# Smart_Lights_X1.net
KiCad netlist of a schematic drawn in EAGLE
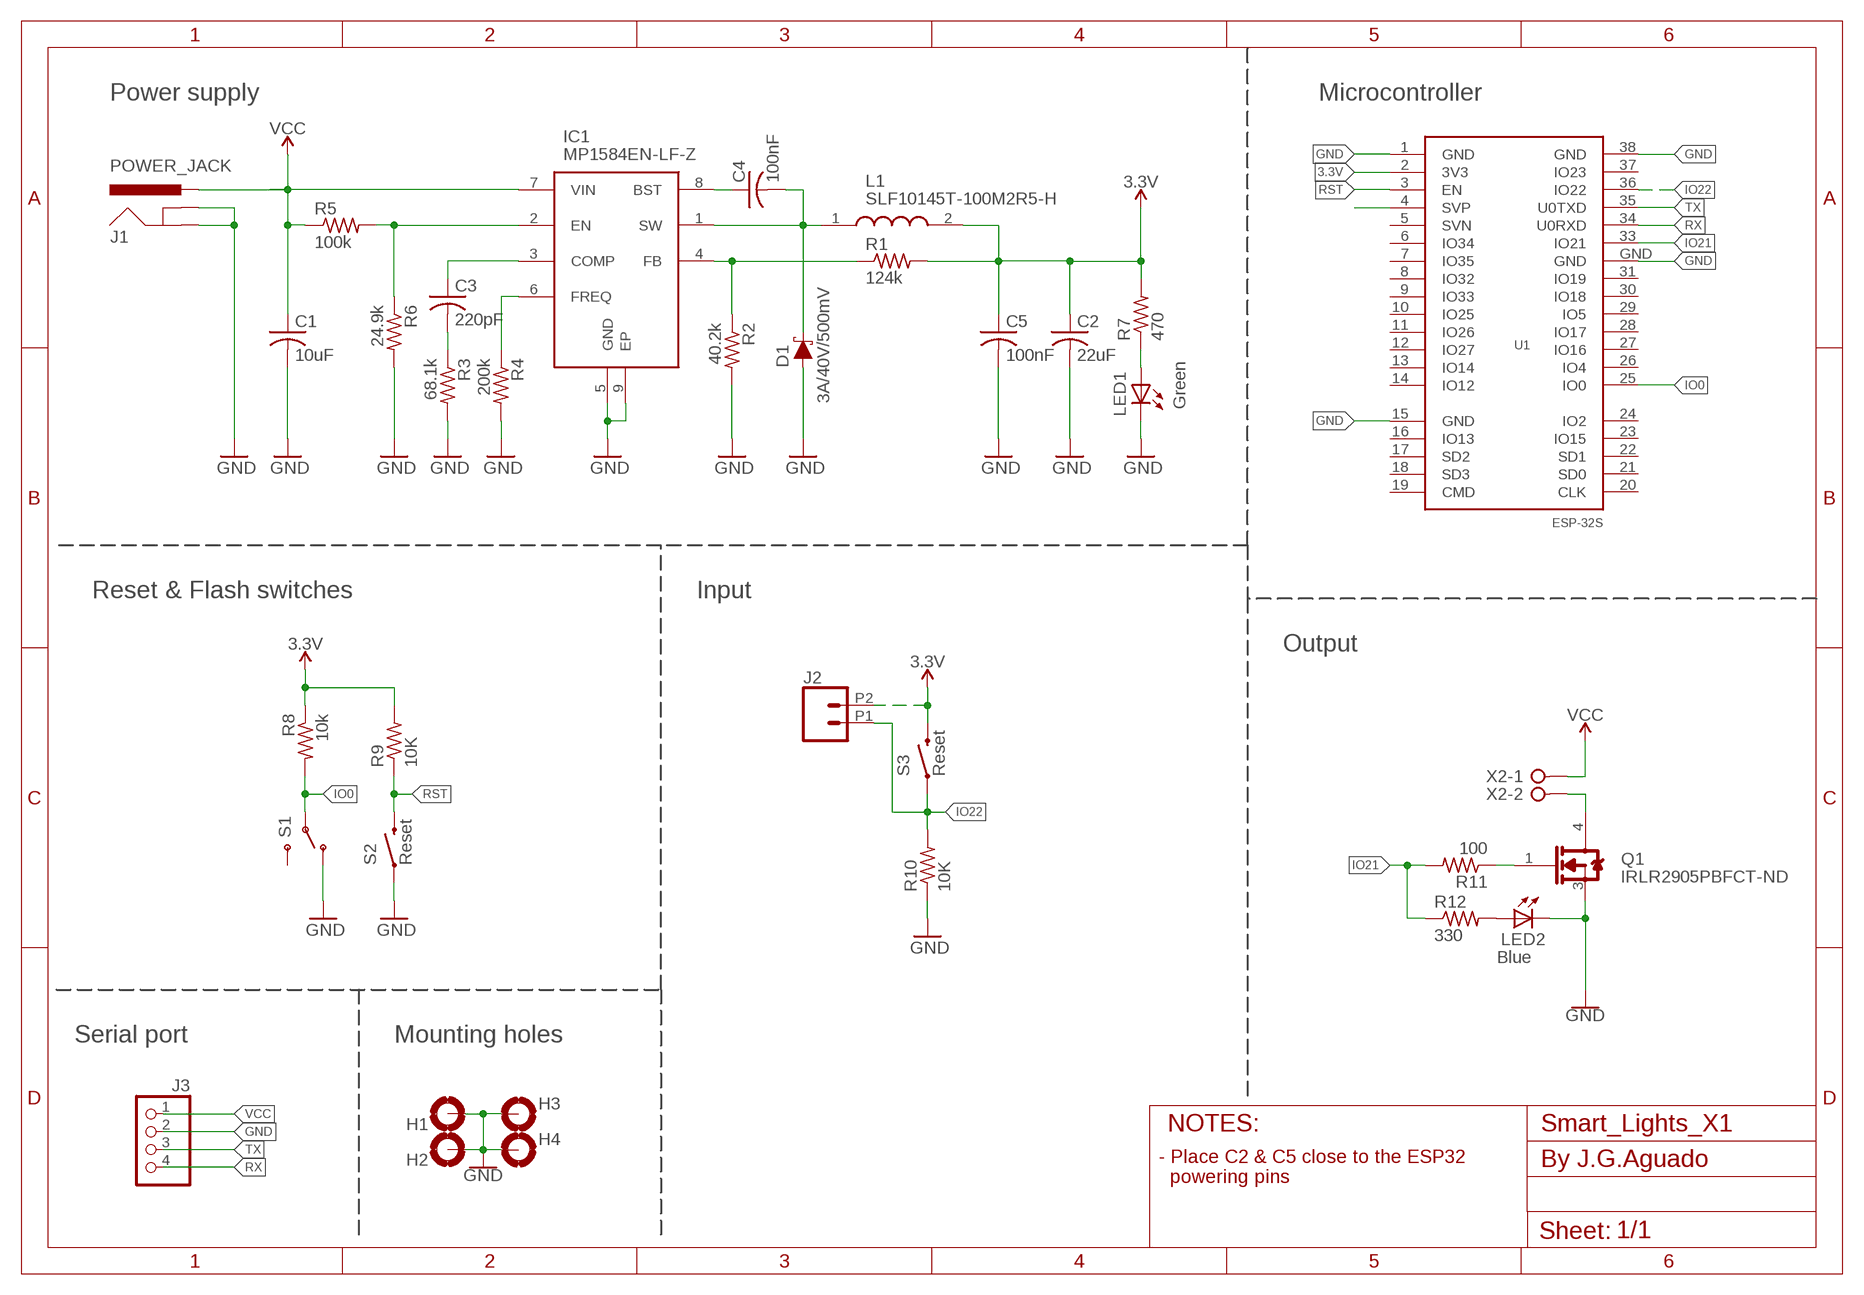
[diagram p0: schematic, sheet 1]

(export (version "E")
  (design (tool "Eeschema 10.0.6"))
  (components
    (comp (ref "C1")
      (value "10uF")
      (footprint "eagle-import:C1206")
      (libsource (lib "eagle-import") (part "C-USC1206"))
    )
    (comp (ref "C2")
      (value "22uF")
      (footprint "eagle-import:C1206")
      (libsource (lib "eagle-import") (part "C-USC1206"))
    )
    (comp (ref "C3")
      (value "220pF")
      (footprint "eagle-import:C1206")
      (libsource (lib "eagle-import") (part "C-USC1206"))
    )
    (comp (ref "C4")
      (value "100nF")
      (footprint "eagle-import:C1206")
      (libsource (lib "eagle-import") (part "C-USC1206"))
    )
    (comp (ref "C5")
      (value "100nF")
      (footprint "eagle-import:C1206")
      (libsource (lib "eagle-import") (part "C-USC1206"))
    )
    (comp (ref "D1")
      (value "3A/40V/500mV")
      (footprint "eagle-import:SMA-DIODE")
      (libsource (lib "eagle-import") (part "DIODE-SCHOTTKY-B340A"))
    )
    (comp (ref "H1")
      (value "MOUNT-PAD-ROUND")
      (footprint "eagle-import:3,0-PAD")
      (libsource (lib "eagle-import") (part "MOUNT-PAD-ROUND"))
    )
    (comp (ref "H2")
      (value "MOUNT-PAD-ROUND")
      (footprint "eagle-import:3,0-PAD")
      (libsource (lib "eagle-import") (part "MOUNT-PAD-ROUND"))
    )
    (comp (ref "H3")
      (value "MOUNT-PAD-ROUND")
      (footprint "eagle-import:3,0-PAD")
      (libsource (lib "eagle-import") (part "MOUNT-PAD-ROUND"))
    )
    (comp (ref "H4")
      (value "MOUNT-PAD-ROUND")
      (footprint "eagle-import:3,0-PAD")
      (libsource (lib "eagle-import") (part "MOUNT-PAD-ROUND"))
    )
    (comp (ref "IC1")
      (value "MP1584EN-LF-Z")
      (footprint "eagle-import:SOIC127P600X170-9N")
      (fields (field (name "MOUSER_PART_NUMBER") "946-MP1584ENLFZ"))
      (libsource (lib "eagle-import") (part "MP1584EN-LF-Z"))
    )
    (comp (ref "J1")
      (value "POWER_JACK")
      (footprint "eagle-import:POWER_JACK_PTH")
      (libsource (lib "eagle-import") (part "POWER_JACK"))
    )
    (comp (ref "J2")
      (value "CONN_022.54MM_SCREWTERM")
      (footprint "eagle-import:1X02_2.54_SCREWTERM")
      (libsource (lib "eagle-import") (part "CONN_022.54MM_SCREWTERM"))
    )
    (comp (ref "J3")
      (value "PINHD-1X4")
      (footprint "eagle-import:1X04")
      (libsource (lib "eagle-import") (part "PINHD-1X4"))
    )
    (comp (ref "L1")
      (value "SLF10145T-100M2R5-H")
      (footprint "eagle-import:SLF10145")
      (fields (field (name "MOUSER_PART_NUMBER") "810-SLF10145T100M2R5"))
      (libsource (lib "eagle-import") (part "SLF10145T-100M2R5-H"))
    )
    (comp (ref "LED1")
      (value "Green")
      (footprint "eagle-import:LED1206")
      (libsource (lib "eagle-import") (part "LED1206"))
    )
    (comp (ref "LED2")
      (value "Blue")
      (footprint "eagle-import:LED1206")
      (libsource (lib "eagle-import") (part "LED1206"))
    )
    (comp (ref "Q1")
      (value "IRLR2905TRPBF")
      (footprint "eagle-import:INFINEON_TECHNOLOGIES_IRLR2905TRPBF_0")
      (fields
        (field (name "DIGIKEY_PART_NUMBER") "IRLR2905PBFCT-ND")
        (field (name "MF") "Infineon Technologies")
        (field (name "MOUSER_PART_NUMBER") "942-IRLR2905TRPBF")
      )
      (libsource (lib "eagle-import") (part "INFINEON_TECHNOLOGIES_IRLR2905TRPBFINFINEON_TECHNOLOGIES_IRLR2905TRPBF_0_0"))
    )
    (comp (ref "R1")
      (value "124k")
      (footprint "eagle-import:M1206")
      (libsource (lib "eagle-import") (part "R-US_M1206"))
    )
    (comp (ref "R2")
      (value "40.2k")
      (footprint "eagle-import:M1206")
      (libsource (lib "eagle-import") (part "R-US_M1206"))
    )
    (comp (ref "R3")
      (value "68.1k")
      (footprint "eagle-import:M1206")
      (libsource (lib "eagle-import") (part "R-US_M1206"))
    )
    (comp (ref "R4")
      (value "200k")
      (footprint "eagle-import:M1206")
      (libsource (lib "eagle-import") (part "R-US_M1206"))
    )
    (comp (ref "R5")
      (value "100k")
      (footprint "eagle-import:M1206")
      (libsource (lib "eagle-import") (part "R-US_M1206"))
    )
    (comp (ref "R6")
      (value "24.9k")
      (footprint "eagle-import:M1206")
      (libsource (lib "eagle-import") (part "R-US_M1206"))
    )
    (comp (ref "R7")
      (value "470")
      (footprint "eagle-import:M1206")
      (libsource (lib "eagle-import") (part "R-US_M1206"))
    )
    (comp (ref "R8")
      (value "10k")
      (footprint "eagle-import:M1206")
      (libsource (lib "eagle-import") (part "R-US_M1206"))
    )
    (comp (ref "R9")
      (value "10K")
      (footprint "eagle-import:M1206")
      (libsource (lib "eagle-import") (part "R-US_M1206"))
    )
    (comp (ref "R10")
      (value "10K")
      (footprint "eagle-import:M1206")
      (libsource (lib "eagle-import") (part "R-US_M1206"))
    )
    (comp (ref "R11")
      (value "100")
      (footprint "eagle-import:M1206")
      (libsource (lib "eagle-import") (part "R-US_M1206"))
    )
    (comp (ref "R12")
      (value "330")
      (footprint "eagle-import:M1206")
      (libsource (lib "eagle-import") (part "R-US_M1206"))
    )
    (comp (ref "S1")
      (value "SWITCH_SPDT")
      (footprint "eagle-import:KPS-1290")
      (libsource (lib "eagle-import") (part "SWITCH_SPDT"))
    )
    (comp (ref "S2")
      (value "Reset")
      (footprint "eagle-import:TACTILE_SWITCH_TALL")
      (libsource (lib "eagle-import") (part "SWITCH-MOMENTARY-2SMD-4"))
    )
    (comp (ref "S3")
      (value "Reset")
      (footprint "eagle-import:TACTILE_SWITCH_TALL")
      (libsource (lib "eagle-import") (part "SWITCH-MOMENTARY-2SMD-4"))
    )
    (comp (ref "U1")
      (value "ESP-32S")
      (footprint "eagle-import:ESP-32S")
      (libsource (lib "eagle-import") (part "ESP-32S"))
    )
    (comp (ref "X2")
      (value "W237-02P")
      (footprint "eagle-import:W237-132")
      (libsource (lib "eagle-import") (part "W237-02P"))
    )
  )
  (nets
    (net (code "1") (name "3.3V") (class "Default")
      (node (ref "C2") (pin "1") (pinfunction "1_1") (pintype "passive"))
      (node (ref "C5") (pin "1") (pinfunction "1_1") (pintype "passive"))
      (node (ref "J2") (pin "P2") (pinfunction "2_P2") (pintype "passive"))
      (node (ref "L1") (pin "2") (pinfunction "2_2") (pintype "bidirectional"))
      (node (ref "R1") (pin "2") (pinfunction "2_2") (pintype "passive"))
      (node (ref "R7") (pin "2") (pinfunction "2_2") (pintype "passive"))
      (node (ref "R8") (pin "1") (pinfunction "1_1") (pintype "passive"))
      (node (ref "R9") (pin "2") (pinfunction "2_2") (pintype "passive"))
      (node (ref "S3") (pin "B2") (pinfunction "2_B2") (pintype "passive"))
      (node (ref "U1") (pin "2") (pinfunction "3V3_2") (pintype "power_in"))
    )
    (net (code "2") (name "GND") (class "Default")
      (node (ref "C1") (pin "2") (pinfunction "2_2") (pintype "passive"))
      (node (ref "C2") (pin "2") (pinfunction "2_2") (pintype "passive"))
      (node (ref "C5") (pin "2") (pinfunction "2_2") (pintype "passive"))
      (node (ref "D1") (pin "A") (pinfunction "A_A") (pintype "passive"))
      (node (ref "H1") (pin "B3,0") (pinfunction "MOUNT_B3,0") (pintype "passive"))
      (node (ref "H1") (pin "P$2") (pinfunction "MOUNT_P$2") (pintype "passive"))
      (node (ref "H1") (pin "P$3") (pinfunction "MOUNT_P$3") (pintype "passive"))
      (node (ref "H1") (pin "P$4") (pinfunction "MOUNT_P$4") (pintype "passive"))
      (node (ref "H1") (pin "P$5") (pinfunction "MOUNT_P$5") (pintype "passive"))
      (node (ref "H1") (pin "P$6") (pinfunction "MOUNT_P$6") (pintype "passive"))
      (node (ref "H1") (pin "P$7") (pinfunction "MOUNT_P$7") (pintype "passive"))
      (node (ref "H1") (pin "P$8") (pinfunction "MOUNT_P$8") (pintype "passive"))
      (node (ref "H1") (pin "P$9") (pinfunction "MOUNT_P$9") (pintype "passive"))
      (node (ref "H2") (pin "B3,0") (pinfunction "MOUNT_B3,0") (pintype "passive"))
      (node (ref "H2") (pin "P$2") (pinfunction "MOUNT_P$2") (pintype "passive"))
      (node (ref "H2") (pin "P$3") (pinfunction "MOUNT_P$3") (pintype "passive"))
      (node (ref "H2") (pin "P$4") (pinfunction "MOUNT_P$4") (pintype "passive"))
      (node (ref "H2") (pin "P$5") (pinfunction "MOUNT_P$5") (pintype "passive"))
      (node (ref "H2") (pin "P$6") (pinfunction "MOUNT_P$6") (pintype "passive"))
      (node (ref "H2") (pin "P$7") (pinfunction "MOUNT_P$7") (pintype "passive"))
      (node (ref "H2") (pin "P$8") (pinfunction "MOUNT_P$8") (pintype "passive"))
      (node (ref "H2") (pin "P$9") (pinfunction "MOUNT_P$9") (pintype "passive"))
      (node (ref "H3") (pin "B3,0") (pinfunction "MOUNT_B3,0") (pintype "passive"))
      (node (ref "H3") (pin "P$2") (pinfunction "MOUNT_P$2") (pintype "passive"))
      (node (ref "H3") (pin "P$3") (pinfunction "MOUNT_P$3") (pintype "passive"))
      (node (ref "H3") (pin "P$4") (pinfunction "MOUNT_P$4") (pintype "passive"))
      (node (ref "H3") (pin "P$5") (pinfunction "MOUNT_P$5") (pintype "passive"))
      (node (ref "H3") (pin "P$6") (pinfunction "MOUNT_P$6") (pintype "passive"))
      (node (ref "H3") (pin "P$7") (pinfunction "MOUNT_P$7") (pintype "passive"))
      (node (ref "H3") (pin "P$8") (pinfunction "MOUNT_P$8") (pintype "passive"))
      (node (ref "H3") (pin "P$9") (pinfunction "MOUNT_P$9") (pintype "passive"))
      (node (ref "H4") (pin "B3,0") (pinfunction "MOUNT_B3,0") (pintype "passive"))
      (node (ref "H4") (pin "P$2") (pinfunction "MOUNT_P$2") (pintype "passive"))
      (node (ref "H4") (pin "P$3") (pinfunction "MOUNT_P$3") (pintype "passive"))
      (node (ref "H4") (pin "P$4") (pinfunction "MOUNT_P$4") (pintype "passive"))
      (node (ref "H4") (pin "P$5") (pinfunction "MOUNT_P$5") (pintype "passive"))
      (node (ref "H4") (pin "P$6") (pinfunction "MOUNT_P$6") (pintype "passive"))
      (node (ref "H4") (pin "P$7") (pinfunction "MOUNT_P$7") (pintype "passive"))
      (node (ref "H4") (pin "P$8") (pinfunction "MOUNT_P$8") (pintype "passive"))
      (node (ref "H4") (pin "P$9") (pinfunction "MOUNT_P$9") (pintype "passive"))
      (node (ref "IC1") (pin "5") (pinfunction "GND_5") (pintype "power_in"))
      (node (ref "IC1") (pin "9") (pinfunction "EP_9") (pintype "bidirectional"))
      (node (ref "J1") (pin "GND") (pinfunction "GND_GND") (pintype "bidirectional"))
      (node (ref "J1") (pin "GNDBREAK") (pinfunction "GNDBREAK_GNDBREAK") (pintype "bidirectional"))
      (node (ref "J3") (pin "2") (pinfunction "2_2") (pintype "passive"))
      (node (ref "LED1") (pin "C") (pinfunction "C_C") (pintype "passive"))
      (node (ref "LED2") (pin "C") (pinfunction "C_C") (pintype "passive"))
      (node (ref "Q1") (pin "3") (pinfunction "SOURCE_3") (pintype "passive"))
      (node (ref "R10") (pin "1") (pinfunction "1_1") (pintype "passive"))
      (node (ref "R2") (pin "2") (pinfunction "2_2") (pintype "passive"))
      (node (ref "R3") (pin "2") (pinfunction "2_2") (pintype "passive"))
      (node (ref "R4") (pin "2") (pinfunction "2_2") (pintype "passive"))
      (node (ref "R6") (pin "2") (pinfunction "2_2") (pintype "passive"))
      (node (ref "S1") (pin "O") (pinfunction "O_O") (pintype "passive"))
      (node (ref "S2") (pin "A2") (pinfunction "1_A2") (pintype "passive"))
      (node (ref "U1") (pin "1") (pinfunction "GND_1") (pintype "power_in"))
      (node (ref "U1") (pin "15") (pinfunction "GND_15") (pintype "power_in"))
      (node (ref "U1") (pin "38") (pinfunction "GND_38") (pintype "power_in"))
      (node (ref "U1") (pin "GND") (pinfunction "GND_GND") (pintype "power_in"))
    )
    (net (code "3") (name "IO0") (class "Default")
      (node (ref "R8") (pin "2") (pinfunction "2_2") (pintype "passive"))
      (node (ref "S1") (pin "P") (pinfunction "P_P") (pintype "passive"))
      (node (ref "U1") (pin "25") (pinfunction "IO0_25") (pintype "bidirectional"))
    )
    (net (code "4") (name "IO21") (class "Default")
      (node (ref "R11") (pin "2") (pinfunction "2_2") (pintype "passive"))
      (node (ref "R12") (pin "1") (pinfunction "1_1") (pintype "passive"))
      (node (ref "U1") (pin "33") (pinfunction "IO21_33") (pintype "bidirectional"))
    )
    (net (code "5") (name "IO22") (class "Default")
      (node (ref "J2") (pin "P1") (pinfunction "1_P1") (pintype "passive"))
      (node (ref "R10") (pin "2") (pinfunction "2_2") (pintype "passive"))
      (node (ref "S3") (pin "A2") (pinfunction "1_A2") (pintype "passive"))
      (node (ref "U1") (pin "36") (pinfunction "IO22_36") (pintype "bidirectional"))
    )
    (net (code "6") (name "Net-(C3-Pad2)") (class "Default")
      (node (ref "C3") (pin "2") (pinfunction "2_2") (pintype "passive"))
      (node (ref "R3") (pin "1") (pinfunction "1_1") (pintype "passive"))
    )
    (net (code "7") (name "Net-(IC1-BST)") (class "Default")
      (node (ref "C4") (pin "1") (pinfunction "1_1") (pintype "passive"))
      (node (ref "IC1") (pin "8") (pinfunction "BST_8") (pintype "input"))
    )
    (net (code "8") (name "Net-(IC1-COMP)") (class "Default")
      (node (ref "C3") (pin "1") (pinfunction "1_1") (pintype "passive"))
      (node (ref "IC1") (pin "3") (pinfunction "COMP_3") (pintype "bidirectional"))
    )
    (net (code "9") (name "Net-(IC1-EN)") (class "Default")
      (node (ref "IC1") (pin "2") (pinfunction "EN_2") (pintype "input"))
      (node (ref "R5") (pin "2") (pinfunction "2_2") (pintype "passive"))
      (node (ref "R6") (pin "1") (pinfunction "1_1") (pintype "passive"))
    )
    (net (code "10") (name "Net-(IC1-FB)") (class "Default")
      (node (ref "IC1") (pin "4") (pinfunction "FB_4") (pintype "input"))
      (node (ref "R1") (pin "1") (pinfunction "1_1") (pintype "passive"))
      (node (ref "R2") (pin "1") (pinfunction "1_1") (pintype "passive"))
    )
    (net (code "11") (name "Net-(IC1-FREQ)") (class "Default")
      (node (ref "IC1") (pin "6") (pinfunction "FREQ_6") (pintype "input"))
      (node (ref "R4") (pin "1") (pinfunction "1_1") (pintype "passive"))
    )
    (net (code "12") (name "Net-(IC1-SW)") (class "Default")
      (node (ref "C4") (pin "2") (pinfunction "2_2") (pintype "passive"))
      (node (ref "D1") (pin "C") (pinfunction "C_C") (pintype "passive"))
      (node (ref "IC1") (pin "1") (pinfunction "SW_1") (pintype "output"))
      (node (ref "L1") (pin "1") (pinfunction "1_1") (pintype "bidirectional"))
    )
    (net (code "13") (name "Net-(LED1-PadA)") (class "Default")
      (node (ref "LED1") (pin "A") (pinfunction "A_A") (pintype "passive"))
      (node (ref "R7") (pin "1") (pinfunction "1_1") (pintype "passive"))
    )
    (net (code "14") (name "Net-(LED2-PadA)") (class "Default")
      (node (ref "LED2") (pin "A") (pinfunction "A_A") (pintype "passive"))
      (node (ref "R12") (pin "2") (pinfunction "2_2") (pintype "passive"))
    )
    (net (code "15") (name "Net-(Q1-DRAIN)") (class "Default")
      (node (ref "Q1") (pin "4") (pinfunction "DRAIN_4") (pintype "passive"))
      (node (ref "X2") (pin "2") (pinfunction "KL_2") (pintype "passive"))
    )
    (net (code "16") (name "Net-(Q1-GATE)") (class "Default")
      (node (ref "Q1") (pin "1") (pinfunction "GATE_1") (pintype "passive"))
      (node (ref "R11") (pin "1") (pinfunction "1_1") (pintype "passive"))
    )
    (net (code "17") (name "RST") (class "Default")
      (node (ref "R9") (pin "1") (pinfunction "1_1") (pintype "passive"))
      (node (ref "S2") (pin "B2") (pinfunction "2_B2") (pintype "passive"))
      (node (ref "U1") (pin "3") (pinfunction "EN_3") (pintype "input"))
    )
    (net (code "18") (name "RX") (class "Default")
      (node (ref "J3") (pin "4") (pinfunction "4_4") (pintype "passive"))
      (node (ref "U1") (pin "34") (pinfunction "U0RXD_34") (pintype "bidirectional"))
    )
    (net (code "19") (name "TX") (class "Default")
      (node (ref "J3") (pin "3") (pinfunction "3_3") (pintype "passive"))
      (node (ref "U1") (pin "35") (pinfunction "U0TXD_35") (pintype "bidirectional"))
    )
    (net (code "20") (name "VCC") (class "Default")
      (node (ref "C1") (pin "1") (pinfunction "1_1") (pintype "passive"))
      (node (ref "IC1") (pin "7") (pinfunction "VIN_7") (pintype "power_in"))
      (node (ref "J1") (pin "PWR") (pinfunction "PWR_PWR") (pintype "bidirectional"))
      (node (ref "J3") (pin "1") (pinfunction "1_1") (pintype "passive"))
      (node (ref "R5") (pin "1") (pinfunction "1_1") (pintype "passive"))
      (node (ref "X2") (pin "1") (pinfunction "KL_1") (pintype "passive"))
    )
    (net (code "21") (name "unconnected-(S1-PadS)") (class "Default")
      (node (ref "S1") (pin "S") (pinfunction "S_S") (pintype "passive"))
    )
    (net (code "22") (name "unconnected-(U1-CLK-Pad20)") (class "Default")
      (node (ref "U1") (pin "20") (pinfunction "CLK_20") (pintype "bidirectional"))
    )
    (net (code "23") (name "unconnected-(U1-CMD-Pad19)") (class "Default")
      (node (ref "U1") (pin "19") (pinfunction "CMD_19") (pintype "bidirectional"))
    )
    (net (code "24") (name "unconnected-(U1-IO2-Pad24)") (class "Default")
      (node (ref "U1") (pin "24") (pinfunction "IO2_24") (pintype "bidirectional"))
    )
    (net (code "25") (name "unconnected-(U1-IO4-Pad26)") (class "Default")
      (node (ref "U1") (pin "26") (pinfunction "IO4_26") (pintype "bidirectional"))
    )
    (net (code "26") (name "unconnected-(U1-IO5-Pad29)") (class "Default")
      (node (ref "U1") (pin "29") (pinfunction "IO5_29") (pintype "bidirectional"))
    )
    (net (code "27") (name "unconnected-(U1-IO12-Pad14)") (class "Default")
      (node (ref "U1") (pin "14") (pinfunction "IO12_14") (pintype "bidirectional"))
    )
    (net (code "28") (name "unconnected-(U1-IO13-Pad16)") (class "Default")
      (node (ref "U1") (pin "16") (pinfunction "IO13_16") (pintype "bidirectional"))
    )
    (net (code "29") (name "unconnected-(U1-IO14-Pad13)") (class "Default")
      (node (ref "U1") (pin "13") (pinfunction "IO14_13") (pintype "bidirectional"))
    )
    (net (code "30") (name "unconnected-(U1-IO15-Pad23)") (class "Default")
      (node (ref "U1") (pin "23") (pinfunction "IO15_23") (pintype "bidirectional"))
    )
    (net (code "31") (name "unconnected-(U1-IO16-Pad27)") (class "Default")
      (node (ref "U1") (pin "27") (pinfunction "IO16_27") (pintype "bidirectional"))
    )
    (net (code "32") (name "unconnected-(U1-IO17-Pad28)") (class "Default")
      (node (ref "U1") (pin "28") (pinfunction "IO17_28") (pintype "bidirectional"))
    )
    (net (code "33") (name "unconnected-(U1-IO18-Pad30)") (class "Default")
      (node (ref "U1") (pin "30") (pinfunction "IO18_30") (pintype "bidirectional"))
    )
    (net (code "34") (name "unconnected-(U1-IO19-Pad31)") (class "Default")
      (node (ref "U1") (pin "31") (pinfunction "IO19_31") (pintype "bidirectional"))
    )
    (net (code "35") (name "unconnected-(U1-IO23-Pad37)") (class "Default")
      (node (ref "U1") (pin "37") (pinfunction "IO23_37") (pintype "bidirectional"))
    )
    (net (code "36") (name "unconnected-(U1-IO25-Pad10)") (class "Default")
      (node (ref "U1") (pin "10") (pinfunction "IO25_10") (pintype "bidirectional"))
    )
    (net (code "37") (name "unconnected-(U1-IO26-Pad11)") (class "Default")
      (node (ref "U1") (pin "11") (pinfunction "IO26_11") (pintype "bidirectional"))
    )
    (net (code "38") (name "unconnected-(U1-IO27-Pad12)") (class "Default")
      (node (ref "U1") (pin "12") (pinfunction "IO27_12") (pintype "bidirectional"))
    )
    (net (code "39") (name "unconnected-(U1-IO32-Pad8)") (class "Default")
      (node (ref "U1") (pin "8") (pinfunction "IO32_8") (pintype "bidirectional"))
    )
    (net (code "40") (name "unconnected-(U1-IO33-Pad9)") (class "Default")
      (node (ref "U1") (pin "9") (pinfunction "IO33_9") (pintype "bidirectional"))
    )
    (net (code "41") (name "unconnected-(U1-IO34-Pad6)") (class "Default")
      (node (ref "U1") (pin "6") (pinfunction "IO34_6") (pintype "bidirectional"))
    )
    (net (code "42") (name "unconnected-(U1-IO35-Pad7)") (class "Default")
      (node (ref "U1") (pin "7") (pinfunction "IO35_7") (pintype "bidirectional"))
    )
    (net (code "43") (name "unconnected-(U1-SD0-Pad21)") (class "Default")
      (node (ref "U1") (pin "21") (pinfunction "SD0_21") (pintype "bidirectional"))
    )
    (net (code "44") (name "unconnected-(U1-SD1-Pad22)") (class "Default")
      (node (ref "U1") (pin "22") (pinfunction "SD1_22") (pintype "bidirectional"))
    )
    (net (code "45") (name "unconnected-(U1-SD2-Pad17)") (class "Default")
      (node (ref "U1") (pin "17") (pinfunction "SD2_17") (pintype "bidirectional"))
    )
    (net (code "46") (name "unconnected-(U1-SD3-Pad18)") (class "Default")
      (node (ref "U1") (pin "18") (pinfunction "SD3_18") (pintype "bidirectional"))
    )
    (net (code "47") (name "unconnected-(U1-SVN-Pad5)") (class "Default")
      (node (ref "U1") (pin "5") (pinfunction "SVN_5") (pintype "bidirectional"))
    )
    (net (code "48") (name "unconnected-(U1-SVP-Pad4)") (class "Default")
      (node (ref "U1") (pin "4") (pinfunction "SVP_4") (pintype "bidirectional"))
    )
  )
)
